# Solder_Training_Tier_1.net
KiCad netlist of a schematic drawn in Altium Designer
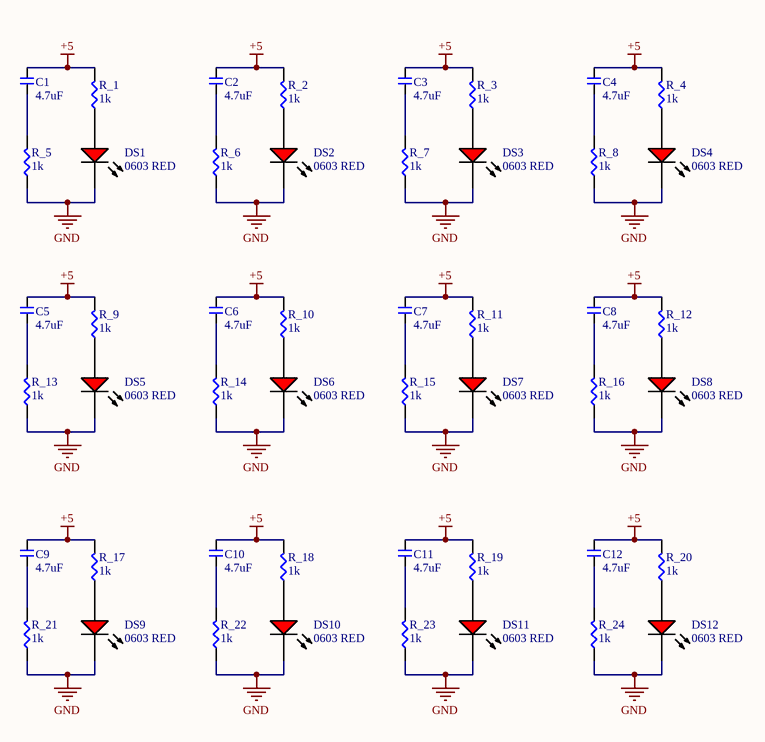
[diagram p0: Solder Training Tier 1.SchDoc]

(export (version "E")
  (design (tool "Eeschema 10.0.6"))
  (components
    (comp (ref "C1")
      (value "4.7uF")
      (footprint "CAP-0603")
      (fields (field (name "SOURCE") "ife19_Elec_Library.SchLib"))
      (libsource (lib "Illini Formula Electric") (part "CAP-0603"))
    )
    (comp (ref "C2")
      (value "4.7uF")
      (footprint "CAP-0603")
      (fields (field (name "SOURCE") "ife19_Elec_Library.SchLib"))
      (libsource (lib "Illini Formula Electric") (part "CAP-0603"))
    )
    (comp (ref "C3")
      (value "4.7uF")
      (footprint "CAP-0603")
      (fields (field (name "SOURCE") "ife19_Elec_Library.SchLib"))
      (libsource (lib "Illini Formula Electric") (part "CAP-0603"))
    )
    (comp (ref "C4")
      (value "4.7uF")
      (footprint "CAP-0603")
      (fields (field (name "SOURCE") "ife19_Elec_Library.SchLib"))
      (libsource (lib "Illini Formula Electric") (part "CAP-0603"))
    )
    (comp (ref "C5")
      (value "4.7uF")
      (footprint "CAP-0603")
      (fields (field (name "SOURCE") "ife19_Elec_Library.SchLib"))
      (libsource (lib "Illini Formula Electric") (part "CAP-0603"))
    )
    (comp (ref "C6")
      (value "4.7uF")
      (footprint "CAP-0603")
      (fields (field (name "SOURCE") "ife19_Elec_Library.SchLib"))
      (libsource (lib "Illini Formula Electric") (part "CAP-0603"))
    )
    (comp (ref "C7")
      (value "4.7uF")
      (footprint "CAP-0603")
      (fields (field (name "SOURCE") "ife19_Elec_Library.SchLib"))
      (libsource (lib "Illini Formula Electric") (part "CAP-0603"))
    )
    (comp (ref "C8")
      (value "4.7uF")
      (footprint "CAP-0603")
      (fields (field (name "SOURCE") "ife19_Elec_Library.SchLib"))
      (libsource (lib "Illini Formula Electric") (part "CAP-0603"))
    )
    (comp (ref "C9")
      (value "4.7uF")
      (footprint "CAP-0603")
      (fields (field (name "SOURCE") "ife19_Elec_Library.SchLib"))
      (libsource (lib "Illini Formula Electric") (part "CAP-0603"))
    )
    (comp (ref "C10")
      (value "4.7uF")
      (footprint "CAP-0603")
      (fields (field (name "SOURCE") "ife19_Elec_Library.SchLib"))
      (libsource (lib "Illini Formula Electric") (part "CAP-0603"))
    )
    (comp (ref "C11")
      (value "4.7uF")
      (footprint "CAP-0603")
      (fields (field (name "SOURCE") "ife19_Elec_Library.SchLib"))
      (libsource (lib "Illini Formula Electric") (part "CAP-0603"))
    )
    (comp (ref "C12")
      (value "4.7uF")
      (footprint "CAP-0603")
      (fields (field (name "SOURCE") "ife19_Elec_Library.SchLib"))
      (libsource (lib "Illini Formula Electric") (part "CAP-0603"))
    )
    (comp (ref "DS1")
      (value "0603 RED")
      (footprint "VISH-TLMX1100_V")
      (description "LED, RED, 2.1 V, -40 to 100 degC, 2-Pin SMD (0603), RoHS, Tape and Reel")
      (fields (field (name "TOLERANCE") "5%"))
      (libsource (lib "Altium Content Vault") (part "LED-RED-AK-2"))
    )
    (comp (ref "DS2")
      (value "0603 RED")
      (footprint "VISH-TLMX1100_V")
      (description "LED, RED, 2.1 V, -40 to 100 degC, 2-Pin SMD (0603), RoHS, Tape and Reel")
      (fields (field (name "TOLERANCE") "5%"))
      (libsource (lib "Altium Content Vault") (part "LED-RED-AK-2"))
    )
    (comp (ref "DS3")
      (value "0603 RED")
      (footprint "VISH-TLMX1100_V")
      (description "LED, RED, 2.1 V, -40 to 100 degC, 2-Pin SMD (0603), RoHS, Tape and Reel")
      (fields (field (name "TOLERANCE") "5%"))
      (libsource (lib "Altium Content Vault") (part "LED-RED-AK-2"))
    )
    (comp (ref "DS4")
      (value "0603 RED")
      (footprint "VISH-TLMX1100_V")
      (description "LED, RED, 2.1 V, -40 to 100 degC, 2-Pin SMD (0603), RoHS, Tape and Reel")
      (fields (field (name "TOLERANCE") "5%"))
      (libsource (lib "Altium Content Vault") (part "LED-RED-AK-2"))
    )
    (comp (ref "DS5")
      (value "0603 RED")
      (footprint "VISH-TLMX1100_V")
      (description "LED, RED, 2.1 V, -40 to 100 degC, 2-Pin SMD (0603), RoHS, Tape and Reel")
      (fields (field (name "TOLERANCE") "5%"))
      (libsource (lib "Altium Content Vault") (part "LED-RED-AK-2"))
    )
    (comp (ref "DS6")
      (value "0603 RED")
      (footprint "VISH-TLMX1100_V")
      (description "LED, RED, 2.1 V, -40 to 100 degC, 2-Pin SMD (0603), RoHS, Tape and Reel")
      (fields (field (name "TOLERANCE") "5%"))
      (libsource (lib "Altium Content Vault") (part "LED-RED-AK-2"))
    )
    (comp (ref "DS7")
      (value "0603 RED")
      (footprint "VISH-TLMX1100_V")
      (description "LED, RED, 2.1 V, -40 to 100 degC, 2-Pin SMD (0603), RoHS, Tape and Reel")
      (fields (field (name "TOLERANCE") "5%"))
      (libsource (lib "Altium Content Vault") (part "LED-RED-AK-2"))
    )
    (comp (ref "DS8")
      (value "0603 RED")
      (footprint "VISH-TLMX1100_V")
      (description "LED, RED, 2.1 V, -40 to 100 degC, 2-Pin SMD (0603), RoHS, Tape and Reel")
      (fields (field (name "TOLERANCE") "5%"))
      (libsource (lib "Altium Content Vault") (part "LED-RED-AK-2"))
    )
    (comp (ref "DS9")
      (value "0603 RED")
      (footprint "VISH-TLMX1100_V")
      (description "LED, RED, 2.1 V, -40 to 100 degC, 2-Pin SMD (0603), RoHS, Tape and Reel")
      (fields (field (name "TOLERANCE") "5%"))
      (libsource (lib "Altium Content Vault") (part "LED-RED-AK-2"))
    )
    (comp (ref "DS10")
      (value "0603 RED")
      (footprint "VISH-TLMX1100_V")
      (description "LED, RED, 2.1 V, -40 to 100 degC, 2-Pin SMD (0603), RoHS, Tape and Reel")
      (fields (field (name "TOLERANCE") "5%"))
      (libsource (lib "Altium Content Vault") (part "LED-RED-AK-2"))
    )
    (comp (ref "DS11")
      (value "0603 RED")
      (footprint "VISH-TLMX1100_V")
      (description "LED, RED, 2.1 V, -40 to 100 degC, 2-Pin SMD (0603), RoHS, Tape and Reel")
      (fields (field (name "TOLERANCE") "5%"))
      (libsource (lib "Altium Content Vault") (part "LED-RED-AK-2"))
    )
    (comp (ref "DS12")
      (value "0603 RED")
      (footprint "VISH-TLMX1100_V")
      (description "LED, RED, 2.1 V, -40 to 100 degC, 2-Pin SMD (0603), RoHS, Tape and Reel")
      (fields (field (name "TOLERANCE") "5%"))
      (libsource (lib "Altium Content Vault") (part "LED-RED-AK-2"))
    )
    (comp (ref "R_1")
      (value "1k")
      (footprint "RES-0603")
      (fields (field (name "SOURCE") "ife19_Elec_Library.SchLib"))
      (libsource (lib "Illini Formula Electric") (part "Symbol"))
    )
    (comp (ref "R_2")
      (value "1k")
      (footprint "RES-0603")
      (fields (field (name "SOURCE") "ife19_Elec_Library.SchLib"))
      (libsource (lib "Illini Formula Electric") (part "Symbol"))
    )
    (comp (ref "R_3")
      (value "1k")
      (footprint "RES-0603")
      (fields (field (name "SOURCE") "ife19_Elec_Library.SchLib"))
      (libsource (lib "Illini Formula Electric") (part "Symbol"))
    )
    (comp (ref "R_4")
      (value "1k")
      (footprint "RES-0603")
      (fields (field (name "SOURCE") "ife19_Elec_Library.SchLib"))
      (libsource (lib "Illini Formula Electric") (part "Symbol"))
    )
    (comp (ref "R_5")
      (value "1k")
      (footprint "RES-0603")
      (fields (field (name "SOURCE") "ife19_Elec_Library.SchLib"))
      (libsource (lib "Illini Formula Electric") (part "Symbol"))
    )
    (comp (ref "R_6")
      (value "1k")
      (footprint "RES-0603")
      (fields (field (name "SOURCE") "ife19_Elec_Library.SchLib"))
      (libsource (lib "Illini Formula Electric") (part "Symbol"))
    )
    (comp (ref "R_7")
      (value "1k")
      (footprint "RES-0603")
      (fields (field (name "SOURCE") "ife19_Elec_Library.SchLib"))
      (libsource (lib "Illini Formula Electric") (part "Symbol"))
    )
    (comp (ref "R_8")
      (value "1k")
      (footprint "RES-0603")
      (fields (field (name "SOURCE") "ife19_Elec_Library.SchLib"))
      (libsource (lib "Illini Formula Electric") (part "Symbol"))
    )
    (comp (ref "R_9")
      (value "1k")
      (footprint "RES-0603")
      (fields (field (name "SOURCE") "ife19_Elec_Library.SchLib"))
      (libsource (lib "Illini Formula Electric") (part "Symbol"))
    )
    (comp (ref "R_10")
      (value "1k")
      (footprint "RES-0603")
      (fields (field (name "SOURCE") "ife19_Elec_Library.SchLib"))
      (libsource (lib "Illini Formula Electric") (part "Symbol"))
    )
    (comp (ref "R_11")
      (value "1k")
      (footprint "RES-0603")
      (fields (field (name "SOURCE") "ife19_Elec_Library.SchLib"))
      (libsource (lib "Illini Formula Electric") (part "Symbol"))
    )
    (comp (ref "R_12")
      (value "1k")
      (footprint "RES-0603")
      (fields (field (name "SOURCE") "ife19_Elec_Library.SchLib"))
      (libsource (lib "Illini Formula Electric") (part "Symbol"))
    )
    (comp (ref "R_13")
      (value "1k")
      (footprint "RES-0603")
      (fields (field (name "SOURCE") "ife19_Elec_Library.SchLib"))
      (libsource (lib "Illini Formula Electric") (part "Symbol"))
    )
    (comp (ref "R_14")
      (value "1k")
      (footprint "RES-0603")
      (fields (field (name "SOURCE") "ife19_Elec_Library.SchLib"))
      (libsource (lib "Illini Formula Electric") (part "Symbol"))
    )
    (comp (ref "R_15")
      (value "1k")
      (footprint "RES-0603")
      (fields (field (name "SOURCE") "ife19_Elec_Library.SchLib"))
      (libsource (lib "Illini Formula Electric") (part "Symbol"))
    )
    (comp (ref "R_16")
      (value "1k")
      (footprint "RES-0603")
      (fields (field (name "SOURCE") "ife19_Elec_Library.SchLib"))
      (libsource (lib "Illini Formula Electric") (part "Symbol"))
    )
    (comp (ref "R_17")
      (value "1k")
      (footprint "RES-0603")
      (fields (field (name "SOURCE") "ife19_Elec_Library.SchLib"))
      (libsource (lib "Illini Formula Electric") (part "Symbol"))
    )
    (comp (ref "R_18")
      (value "1k")
      (footprint "RES-0603")
      (fields (field (name "SOURCE") "ife19_Elec_Library.SchLib"))
      (libsource (lib "Illini Formula Electric") (part "Symbol"))
    )
    (comp (ref "R_19")
      (value "1k")
      (footprint "RES-0603")
      (fields (field (name "SOURCE") "ife19_Elec_Library.SchLib"))
      (libsource (lib "Illini Formula Electric") (part "Symbol"))
    )
    (comp (ref "R_20")
      (value "1k")
      (footprint "RES-0603")
      (fields (field (name "SOURCE") "ife19_Elec_Library.SchLib"))
      (libsource (lib "Illini Formula Electric") (part "Symbol"))
    )
    (comp (ref "R_21")
      (value "1k")
      (footprint "RES-0603")
      (fields (field (name "SOURCE") "ife19_Elec_Library.SchLib"))
      (libsource (lib "Illini Formula Electric") (part "Symbol"))
    )
    (comp (ref "R_22")
      (value "1k")
      (footprint "RES-0603")
      (fields (field (name "SOURCE") "ife19_Elec_Library.SchLib"))
      (libsource (lib "Illini Formula Electric") (part "Symbol"))
    )
    (comp (ref "R_23")
      (value "1k")
      (footprint "RES-0603")
      (fields (field (name "SOURCE") "ife19_Elec_Library.SchLib"))
      (libsource (lib "Illini Formula Electric") (part "Symbol"))
    )
    (comp (ref "R_24")
      (value "1k")
      (footprint "RES-0603")
      (fields (field (name "SOURCE") "ife19_Elec_Library.SchLib"))
      (libsource (lib "Illini Formula Electric") (part "Symbol"))
    )
  )
  (nets
    (net (code "1") (name "+5") (class "Default")
      (node (ref "C1") (pin "2") (pinfunction "2_2") (pintype "passive"))
      (node (ref "C10") (pin "2") (pinfunction "2_2") (pintype "passive"))
      (node (ref "C11") (pin "2") (pinfunction "2_2") (pintype "passive"))
      (node (ref "C12") (pin "2") (pinfunction "2_2") (pintype "passive"))
      (node (ref "C2") (pin "2") (pinfunction "2_2") (pintype "passive"))
      (node (ref "C3") (pin "2") (pinfunction "2_2") (pintype "passive"))
      (node (ref "C4") (pin "2") (pinfunction "2_2") (pintype "passive"))
      (node (ref "C5") (pin "2") (pinfunction "2_2") (pintype "passive"))
      (node (ref "C6") (pin "2") (pinfunction "2_2") (pintype "passive"))
      (node (ref "C7") (pin "2") (pinfunction "2_2") (pintype "passive"))
      (node (ref "C8") (pin "2") (pinfunction "2_2") (pintype "passive"))
      (node (ref "C9") (pin "2") (pinfunction "2_2") (pintype "passive"))
      (node (ref "R_1") (pin "2") (pinfunction "2_2") (pintype "passive"))
      (node (ref "R_10") (pin "2") (pinfunction "2_2") (pintype "passive"))
      (node (ref "R_11") (pin "2") (pinfunction "2_2") (pintype "passive"))
      (node (ref "R_12") (pin "2") (pinfunction "2_2") (pintype "passive"))
      (node (ref "R_17") (pin "2") (pinfunction "2_2") (pintype "passive"))
      (node (ref "R_18") (pin "2") (pinfunction "2_2") (pintype "passive"))
      (node (ref "R_19") (pin "2") (pinfunction "2_2") (pintype "passive"))
      (node (ref "R_2") (pin "2") (pinfunction "2_2") (pintype "passive"))
      (node (ref "R_20") (pin "2") (pinfunction "2_2") (pintype "passive"))
      (node (ref "R_3") (pin "2") (pinfunction "2_2") (pintype "passive"))
      (node (ref "R_4") (pin "2") (pinfunction "2_2") (pintype "passive"))
      (node (ref "R_9") (pin "2") (pinfunction "2_2") (pintype "passive"))
    )
    (net (code "2") (name "GND") (class "Default")
      (node (ref "DS1") (pin "2") (pinfunction "K_2") (pintype "passive"))
      (node (ref "DS10") (pin "2") (pinfunction "K_2") (pintype "passive"))
      (node (ref "DS11") (pin "2") (pinfunction "K_2") (pintype "passive"))
      (node (ref "DS12") (pin "2") (pinfunction "K_2") (pintype "passive"))
      (node (ref "DS2") (pin "2") (pinfunction "K_2") (pintype "passive"))
      (node (ref "DS3") (pin "2") (pinfunction "K_2") (pintype "passive"))
      (node (ref "DS4") (pin "2") (pinfunction "K_2") (pintype "passive"))
      (node (ref "DS5") (pin "2") (pinfunction "K_2") (pintype "passive"))
      (node (ref "DS6") (pin "2") (pinfunction "K_2") (pintype "passive"))
      (node (ref "DS7") (pin "2") (pinfunction "K_2") (pintype "passive"))
      (node (ref "DS8") (pin "2") (pinfunction "K_2") (pintype "passive"))
      (node (ref "DS9") (pin "2") (pinfunction "K_2") (pintype "passive"))
      (node (ref "R_13") (pin "1") (pinfunction "1_1") (pintype "passive"))
      (node (ref "R_14") (pin "1") (pinfunction "1_1") (pintype "passive"))
      (node (ref "R_15") (pin "1") (pinfunction "1_1") (pintype "passive"))
      (node (ref "R_16") (pin "1") (pinfunction "1_1") (pintype "passive"))
      (node (ref "R_21") (pin "1") (pinfunction "1_1") (pintype "passive"))
      (node (ref "R_22") (pin "1") (pinfunction "1_1") (pintype "passive"))
      (node (ref "R_23") (pin "1") (pinfunction "1_1") (pintype "passive"))
      (node (ref "R_24") (pin "1") (pinfunction "1_1") (pintype "passive"))
      (node (ref "R_5") (pin "1") (pinfunction "1_1") (pintype "passive"))
      (node (ref "R_6") (pin "1") (pinfunction "1_1") (pintype "passive"))
      (node (ref "R_7") (pin "1") (pinfunction "1_1") (pintype "passive"))
      (node (ref "R_8") (pin "1") (pinfunction "1_1") (pintype "passive"))
    )
    (net (code "3") (name "Net-(C1-Pad1)") (class "Default")
      (node (ref "C1") (pin "1") (pinfunction "1_1") (pintype "passive"))
      (node (ref "R_5") (pin "2") (pinfunction "2_2") (pintype "passive"))
    )
    (net (code "4") (name "Net-(C2-Pad1)") (class "Default")
      (node (ref "C2") (pin "1") (pinfunction "1_1") (pintype "passive"))
      (node (ref "R_6") (pin "2") (pinfunction "2_2") (pintype "passive"))
    )
    (net (code "5") (name "Net-(C3-Pad1)") (class "Default")
      (node (ref "C3") (pin "1") (pinfunction "1_1") (pintype "passive"))
      (node (ref "R_7") (pin "2") (pinfunction "2_2") (pintype "passive"))
    )
    (net (code "6") (name "Net-(C4-Pad1)") (class "Default")
      (node (ref "C4") (pin "1") (pinfunction "1_1") (pintype "passive"))
      (node (ref "R_8") (pin "2") (pinfunction "2_2") (pintype "passive"))
    )
    (net (code "7") (name "Net-(C5-Pad1)") (class "Default")
      (node (ref "C5") (pin "1") (pinfunction "1_1") (pintype "passive"))
      (node (ref "R_13") (pin "2") (pinfunction "2_2") (pintype "passive"))
    )
    (net (code "8") (name "Net-(C6-Pad1)") (class "Default")
      (node (ref "C6") (pin "1") (pinfunction "1_1") (pintype "passive"))
      (node (ref "R_14") (pin "2") (pinfunction "2_2") (pintype "passive"))
    )
    (net (code "9") (name "Net-(C7-Pad1)") (class "Default")
      (node (ref "C7") (pin "1") (pinfunction "1_1") (pintype "passive"))
      (node (ref "R_15") (pin "2") (pinfunction "2_2") (pintype "passive"))
    )
    (net (code "10") (name "Net-(C8-Pad1)") (class "Default")
      (node (ref "C8") (pin "1") (pinfunction "1_1") (pintype "passive"))
      (node (ref "R_16") (pin "2") (pinfunction "2_2") (pintype "passive"))
    )
    (net (code "11") (name "Net-(C9-Pad1)") (class "Default")
      (node (ref "C9") (pin "1") (pinfunction "1_1") (pintype "passive"))
      (node (ref "R_21") (pin "2") (pinfunction "2_2") (pintype "passive"))
    )
    (net (code "12") (name "Net-(C10-Pad1)") (class "Default")
      (node (ref "C10") (pin "1") (pinfunction "1_1") (pintype "passive"))
      (node (ref "R_22") (pin "2") (pinfunction "2_2") (pintype "passive"))
    )
    (net (code "13") (name "Net-(C11-Pad1)") (class "Default")
      (node (ref "C11") (pin "1") (pinfunction "1_1") (pintype "passive"))
      (node (ref "R_23") (pin "2") (pinfunction "2_2") (pintype "passive"))
    )
    (net (code "14") (name "Net-(C12-Pad1)") (class "Default")
      (node (ref "C12") (pin "1") (pinfunction "1_1") (pintype "passive"))
      (node (ref "R_24") (pin "2") (pinfunction "2_2") (pintype "passive"))
    )
    (net (code "15") (name "Net-(DS1-A)") (class "Default")
      (node (ref "DS1") (pin "1") (pinfunction "A_1") (pintype "passive"))
      (node (ref "R_1") (pin "1") (pinfunction "1_1") (pintype "passive"))
    )
    (net (code "16") (name "Net-(DS2-A)") (class "Default")
      (node (ref "DS2") (pin "1") (pinfunction "A_1") (pintype "passive"))
      (node (ref "R_2") (pin "1") (pinfunction "1_1") (pintype "passive"))
    )
    (net (code "17") (name "Net-(DS3-A)") (class "Default")
      (node (ref "DS3") (pin "1") (pinfunction "A_1") (pintype "passive"))
      (node (ref "R_3") (pin "1") (pinfunction "1_1") (pintype "passive"))
    )
    (net (code "18") (name "Net-(DS4-A)") (class "Default")
      (node (ref "DS4") (pin "1") (pinfunction "A_1") (pintype "passive"))
      (node (ref "R_4") (pin "1") (pinfunction "1_1") (pintype "passive"))
    )
    (net (code "19") (name "Net-(DS5-A)") (class "Default")
      (node (ref "DS5") (pin "1") (pinfunction "A_1") (pintype "passive"))
      (node (ref "R_9") (pin "1") (pinfunction "1_1") (pintype "passive"))
    )
    (net (code "20") (name "Net-(DS6-A)") (class "Default")
      (node (ref "DS6") (pin "1") (pinfunction "A_1") (pintype "passive"))
      (node (ref "R_10") (pin "1") (pinfunction "1_1") (pintype "passive"))
    )
    (net (code "21") (name "Net-(DS7-A)") (class "Default")
      (node (ref "DS7") (pin "1") (pinfunction "A_1") (pintype "passive"))
      (node (ref "R_11") (pin "1") (pinfunction "1_1") (pintype "passive"))
    )
    (net (code "22") (name "Net-(DS8-A)") (class "Default")
      (node (ref "DS8") (pin "1") (pinfunction "A_1") (pintype "passive"))
      (node (ref "R_12") (pin "1") (pinfunction "1_1") (pintype "passive"))
    )
    (net (code "23") (name "Net-(DS9-A)") (class "Default")
      (node (ref "DS9") (pin "1") (pinfunction "A_1") (pintype "passive"))
      (node (ref "R_17") (pin "1") (pinfunction "1_1") (pintype "passive"))
    )
    (net (code "24") (name "Net-(DS10-A)") (class "Default")
      (node (ref "DS10") (pin "1") (pinfunction "A_1") (pintype "passive"))
      (node (ref "R_18") (pin "1") (pinfunction "1_1") (pintype "passive"))
    )
    (net (code "25") (name "Net-(DS11-A)") (class "Default")
      (node (ref "DS11") (pin "1") (pinfunction "A_1") (pintype "passive"))
      (node (ref "R_19") (pin "1") (pinfunction "1_1") (pintype "passive"))
    )
    (net (code "26") (name "Net-(DS12-A)") (class "Default")
      (node (ref "DS12") (pin "1") (pinfunction "A_1") (pintype "passive"))
      (node (ref "R_20") (pin "1") (pinfunction "1_1") (pintype "passive"))
    )
  )
)
